# water-meter.net
KiCad netlist of a schematic drawn in Altium Designer
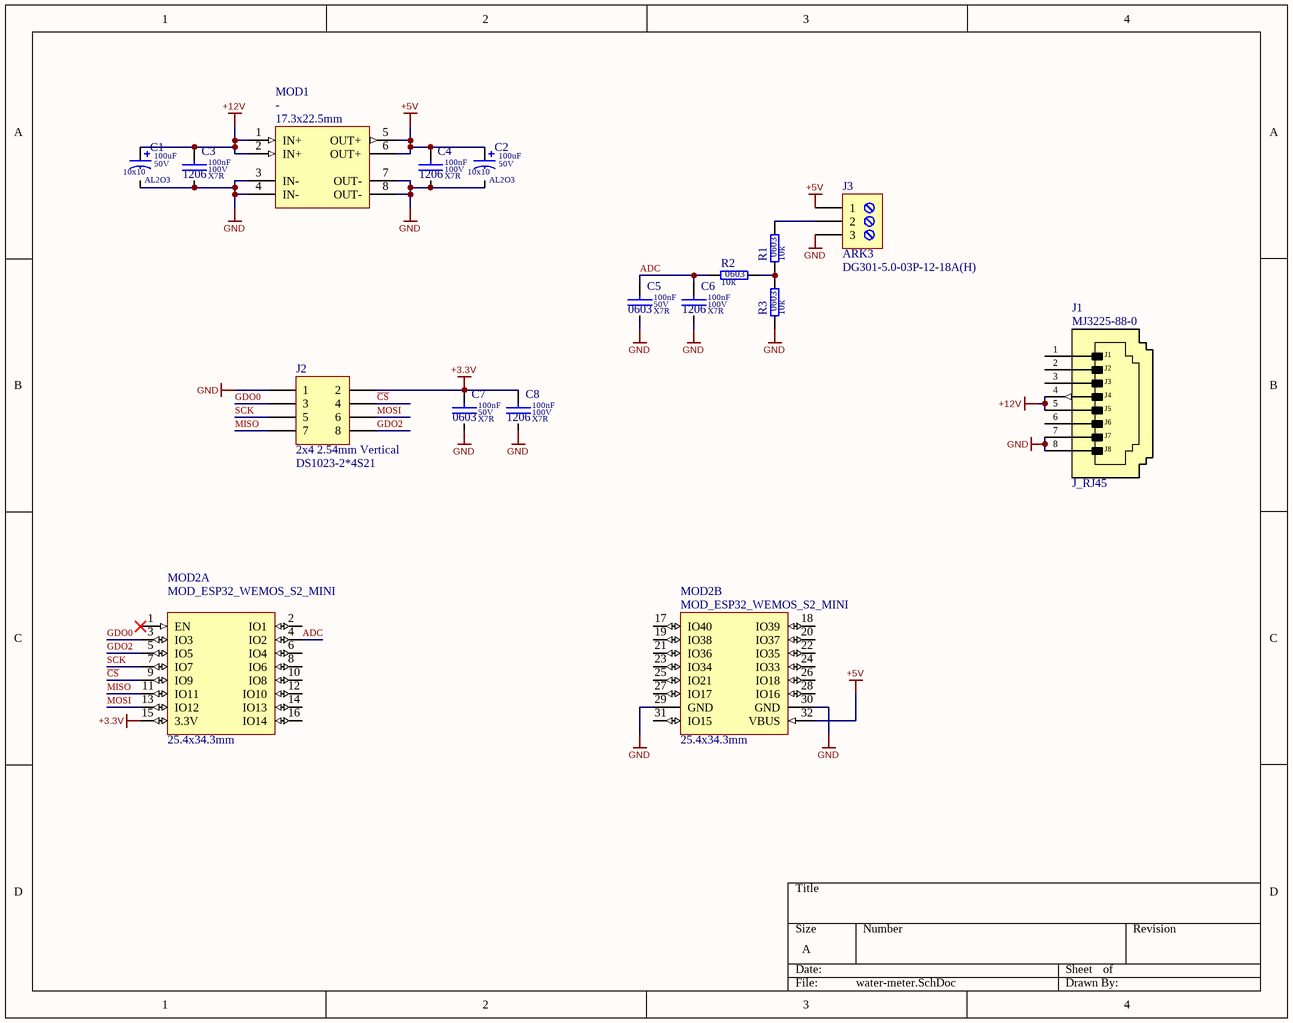
[diagram p0: water-meter.SchDoc]

(export (version "E")
  (design (tool "Eeschema 10.0.6"))
  (components
    (comp (ref "C1")
      (value "100uF")
      (footprint "CE_D_10x10_SMD")
      (description "Polarized Capacitor")
      (fields
        (field (name "DIELECTRIC") "AL2O3")
        (field (name "SCH_FOOTPRINT") "10x10")
        (field (name "VOLTAGE") "50V")
        (field (name "PART NUMBER") "CE_100uF_50V_AL2O3_10x10_20")
        (field (name "MANUFACTURER") "Nichicon")
      )
      (libsource (lib "Library") (part "CE"))
    )
    (comp (ref "C2")
      (value "100uF")
      (footprint "CE_D_10x10_SMD")
      (description "Polarized Capacitor")
      (fields
        (field (name "DIELECTRIC") "AL2O3")
        (field (name "SCH_FOOTPRINT") "10x10")
        (field (name "VOLTAGE") "50V")
        (field (name "PART NUMBER") "CE_100uF_50V_AL2O3_10x10_20")
        (field (name "MANUFACTURER") "Nichicon")
      )
      (libsource (lib "Library") (part "CE"))
    )
    (comp (ref "C3")
      (value "100nF")
      (footprint "C_1206_3216")
      (description "Capacitor")
      (fields
        (field (name "DIELECTRIC") "X7R")
        (field (name "VOLTAGE") "100V")
        (field (name "SCH_FOOTPRINT") "1206")
        (field (name "PART NUMBER") "C_100nF_100V_X7R_1206_10")
        (field (name "MANUFACTURER") "Samsung")
      )
      (libsource (lib "Library") (part "C"))
    )
    (comp (ref "C4")
      (value "100nF")
      (footprint "C_1206_3216")
      (description "Capacitor")
      (fields
        (field (name "DIELECTRIC") "X7R")
        (field (name "VOLTAGE") "100V")
        (field (name "SCH_FOOTPRINT") "1206")
        (field (name "PART NUMBER") "C_100nF_100V_X7R_1206_10")
        (field (name "MANUFACTURER") "Samsung")
      )
      (libsource (lib "Library") (part "C"))
    )
    (comp (ref "C5")
      (value "100nF")
      (footprint "C_0603_1608")
      (description "Capacitor")
      (fields
        (field (name "DIELECTRIC") "X7R")
        (field (name "VOLTAGE") "50V")
        (field (name "SCH_FOOTPRINT") "0603")
        (field (name "PART NUMBER") "C_100nF_50V_X7R_0603_10_AECQ1")
        (field (name "MANUFACTURER") "Murata")
      )
      (libsource (lib "Library") (part "C"))
    )
    (comp (ref "C6")
      (value "100nF")
      (footprint "C_1206_3216")
      (description "Capacitor")
      (fields
        (field (name "DIELECTRIC") "X7R")
        (field (name "VOLTAGE") "100V")
        (field (name "SCH_FOOTPRINT") "1206")
        (field (name "PART NUMBER") "C_100nF_100V_X7R_1206_10")
        (field (name "MANUFACTURER") "Samsung")
      )
      (libsource (lib "Library") (part "C"))
    )
    (comp (ref "C7")
      (value "100nF")
      (footprint "C_0603_1608")
      (description "Capacitor")
      (fields
        (field (name "DIELECTRIC") "X7R")
        (field (name "VOLTAGE") "50V")
        (field (name "SCH_FOOTPRINT") "0603")
        (field (name "PART NUMBER") "C_100nF_50V_X7R_0603_10_AECQ1")
        (field (name "MANUFACTURER") "Murata")
      )
      (libsource (lib "Library") (part "C"))
    )
    (comp (ref "C8")
      (value "100nF")
      (footprint "C_1206_3216")
      (description "Capacitor")
      (fields
        (field (name "DIELECTRIC") "X7R")
        (field (name "VOLTAGE") "100V")
        (field (name "SCH_FOOTPRINT") "1206")
        (field (name "PART NUMBER") "C_100nF_100V_X7R_1206_10")
        (field (name "MANUFACTURER") "Samsung")
      )
      (libsource (lib "Library") (part "C"))
    )
    (comp (ref "J1")
      (value "MJ3225-88-0")
      (footprint "J_RJ45_MJ3225-88-0")
      (fields
        (field (name "SCH_FOOTPRINT") "J_RJ45")
        (field (name "PART NUMBER") "J_RJ45_MJ3225-88-0")
        (field (name "MANUFACTURER") "Global Connector Technology")
        (field (name "Comment") "Modular Connector, Modular Jack, 1 x 1 (Port), 8P8C, Cat3")
      )
      (libsource (lib "Library") (part "J_RJ45"))
    )
    (comp (ref "J2")
      (value "DS1023-2*4S21")
      (footprint "J_HEADER_2x4_2.54_VERTICAL")
      (description "Pin Header")
      (fields
        (field (name "SCH_FOOTPRINT") "2x4 2.54mm Vertical")
        (field (name "PART NUMBER") "J_HEADER_2x4_2.54_VERTICAL")
        (field (name "MANUFACTURER") "Connfly")
      )
      (libsource (lib "Library") (part "J_HEADER_2x4"))
    )
    (comp (ref "J3")
      (value "DG301-5.0-03P-12-18A(H)")
      (footprint "J_ARK3")
      (description "ARK Screw terminal, 3-Pin")
      (fields
        (field (name "SCH_FOOTPRINT") "ARK3")
        (field (name "PART NUMBER") "J_TB-5.0-P-3P")
        (field (name "MANUFACTURER") "DEGSON ELECTRONICS")
      )
      (libsource (lib "Library") (part "J_ARK3"))
    )
    (comp (ref "MOD1")
      (value "-")
      (footprint "MOD_BUCK_MP1584")
      (fields
        (field (name "SCH_FOOTPRINT") "17.3x22.5mm")
        (field (name "PART NUMBER") "MOD_BUCK_MP1584")
        (field (name "Comment") "Low cost, Aliexpress-ready DC-DC buck converter using MP1584")
      )
      (libsource (lib "Library") (part "MOD_BUCK_MP1584"))
    )
    (comp (ref "MOD2")
      (value "MOD_ESP32_WEMOS_S2_MINI")
      (footprint "MOD_ESP32_WEMOS_S2_MINI")
      (fields
        (field (name "SCH_FOOTPRINT") "25.4x34.3mm")
        (field (name "MANUFACTURER") "Wemos")
        (field (name "Comment") "ESP32-S2FN4R2 mini wifi board")
      )
      (libsource (lib "Library") (part "MOD_ESP32_WEMOS_S2_MINI"))
    )
    (comp (ref "R1")
      (value "10k")
      (footprint "R_0603_1608")
      (fields
        (field (name "SCH_FOOTPRINT") "0603")
        (field (name "PART NUMBER") "R_10k_0603_1_AECQ0")
        (field (name "VOLTAGE") "75V")
        (field (name "POWER") "100mW")
      )
      (libsource (lib "Library") (part "R"))
    )
    (comp (ref "R2")
      (value "10k")
      (footprint "R_0603_1608")
      (fields
        (field (name "SCH_FOOTPRINT") "0603")
        (field (name "PART NUMBER") "R_10k_0603_1_AECQ0")
        (field (name "VOLTAGE") "75V")
        (field (name "POWER") "100mW")
      )
      (libsource (lib "Library") (part "R"))
    )
    (comp (ref "R3")
      (value "10k")
      (footprint "R_0603_1608")
      (fields
        (field (name "SCH_FOOTPRINT") "0603")
        (field (name "PART NUMBER") "R_10k_0603_1_AECQ0")
        (field (name "VOLTAGE") "75V")
        (field (name "POWER") "100mW")
      )
      (libsource (lib "Library") (part "R"))
    )
  )
  (nets
    (net (code "1") (name "+3.3V") (class "Default")
      (node (ref "C7") (pin "1") (pinfunction "1_1") (pintype "passive"))
      (node (ref "C8") (pin "1") (pinfunction "1_1") (pintype "passive"))
      (node (ref "J2") (pin "2") (pinfunction "2_2") (pintype "passive"))
      (node (ref "MOD2") (pin "15") (pinfunction "3.3V_15") (pintype "bidirectional"))
    )
    (net (code "2") (name "+5V") (class "Default")
      (node (ref "C2") (pin "1") (pinfunction "1_1") (pintype "passive"))
      (node (ref "C4") (pin "1") (pinfunction "1_1") (pintype "passive"))
      (node (ref "J3") (pin "1") (pinfunction "1_1") (pintype "passive"))
      (node (ref "MOD1") (pin "5") (pinfunction "OUT+_5") (pintype "output"))
      (node (ref "MOD1") (pin "6") (pinfunction "OUT+_6") (pintype "passive"))
      (node (ref "MOD2") (pin "32") (pinfunction "VBUS_32") (pintype "input"))
    )
    (net (code "3") (name "+12V") (class "Default")
      (node (ref "C1") (pin "1") (pinfunction "1_1") (pintype "passive"))
      (node (ref "C3") (pin "1") (pinfunction "1_1") (pintype "passive"))
      (node (ref "J1") (pin "4") (pintype "output"))
      (node (ref "J1") (pin "5") (pintype "passive"))
      (node (ref "MOD1") (pin "1") (pinfunction "IN+_1") (pintype "input"))
      (node (ref "MOD1") (pin "2") (pinfunction "IN+_2") (pintype "input"))
    )
    (net (code "4") (name "/ADC") (class "Default")
      (node (ref "C5") (pin "1") (pinfunction "1_1") (pintype "passive"))
      (node (ref "C6") (pin "1") (pinfunction "1_1") (pintype "passive"))
      (node (ref "MOD2") (pin "4") (pinfunction "IO2_4") (pintype "bidirectional"))
      (node (ref "R2") (pin "1") (pinfunction "1_1") (pintype "passive"))
    )
    (net (code "5") (name "/CS") (class "Default")
      (node (ref "J2") (pin "4") (pinfunction "4_4") (pintype "passive"))
      (node (ref "MOD2") (pin "9") (pinfunction "IO9_9") (pintype "bidirectional"))
    )
    (net (code "6") (name "/GDO0") (class "Default")
      (node (ref "J2") (pin "3") (pinfunction "3_3") (pintype "passive"))
      (node (ref "MOD2") (pin "3") (pinfunction "IO3_3") (pintype "bidirectional"))
    )
    (net (code "7") (name "/GDO2") (class "Default")
      (node (ref "J2") (pin "8") (pinfunction "8_8") (pintype "passive"))
      (node (ref "MOD2") (pin "5") (pinfunction "IO5_5") (pintype "bidirectional"))
    )
    (net (code "8") (name "/MISO") (class "Default")
      (node (ref "J2") (pin "7") (pinfunction "7_7") (pintype "passive"))
      (node (ref "MOD2") (pin "11") (pinfunction "IO11_11") (pintype "bidirectional"))
    )
    (net (code "9") (name "/MOSI") (class "Default")
      (node (ref "J2") (pin "6") (pinfunction "6_6") (pintype "passive"))
      (node (ref "MOD2") (pin "13") (pinfunction "IO12_13") (pintype "bidirectional"))
    )
    (net (code "10") (name "/SCK") (class "Default")
      (node (ref "J2") (pin "5") (pinfunction "5_5") (pintype "passive"))
      (node (ref "MOD2") (pin "7") (pinfunction "IO7_7") (pintype "bidirectional"))
    )
    (net (code "11") (name "GND") (class "Default")
      (node (ref "C1") (pin "2") (pinfunction "2_2") (pintype "passive"))
      (node (ref "C2") (pin "2") (pinfunction "2_2") (pintype "passive"))
      (node (ref "C3") (pin "2") (pinfunction "2_2") (pintype "passive"))
      (node (ref "C4") (pin "2") (pinfunction "2_2") (pintype "passive"))
      (node (ref "C5") (pin "2") (pinfunction "2_2") (pintype "passive"))
      (node (ref "C6") (pin "2") (pinfunction "2_2") (pintype "passive"))
      (node (ref "C7") (pin "2") (pinfunction "2_2") (pintype "passive"))
      (node (ref "C8") (pin "2") (pinfunction "2_2") (pintype "passive"))
      (node (ref "J1") (pin "7") (pintype "passive"))
      (node (ref "J1") (pin "8") (pintype "passive"))
      (node (ref "J2") (pin "1") (pinfunction "1_1") (pintype "passive"))
      (node (ref "J3") (pin "3") (pinfunction "3_3") (pintype "passive"))
      (node (ref "MOD1") (pin "3") (pinfunction "IN-_3") (pintype "power_in"))
      (node (ref "MOD1") (pin "4") (pinfunction "IN-_4") (pintype "power_in"))
      (node (ref "MOD1") (pin "7") (pinfunction "OUT-_7") (pintype "power_in"))
      (node (ref "MOD1") (pin "8") (pinfunction "OUT-_8") (pintype "power_in"))
      (node (ref "MOD2") (pin "29") (pinfunction "GND_29") (pintype "power_in"))
      (node (ref "MOD2") (pin "30") (pinfunction "GND_30") (pintype "power_in"))
      (node (ref "R3") (pin "1") (pinfunction "1_1") (pintype "passive"))
    )
    (net (code "12") (name "Net-(J3-Pad2)") (class "Default")
      (node (ref "J3") (pin "2") (pinfunction "2_2") (pintype "passive"))
      (node (ref "R1") (pin "2") (pinfunction "2_2") (pintype "passive"))
    )
    (net (code "13") (name "Net-(R1-Pad1)") (class "Default")
      (node (ref "R1") (pin "1") (pinfunction "1_1") (pintype "passive"))
      (node (ref "R2") (pin "2") (pinfunction "2_2") (pintype "passive"))
      (node (ref "R3") (pin "2") (pinfunction "2_2") (pintype "passive"))
    )
    (net (code "14") (name "unconnected-(J1-Pad1)") (class "Default")
      (node (ref "J1") (pin "1") (pintype "passive"))
    )
    (net (code "15") (name "unconnected-(J1-Pad2)") (class "Default")
      (node (ref "J1") (pin "2") (pintype "passive"))
    )
    (net (code "16") (name "unconnected-(J1-Pad3)") (class "Default")
      (node (ref "J1") (pin "3") (pintype "passive"))
    )
    (net (code "17") (name "unconnected-(J1-Pad6)") (class "Default")
      (node (ref "J1") (pin "6") (pintype "passive"))
    )
    (net (code "18") (name "unconnected-(MOD2A-EN-Pad1)") (class "Default")
      (node (ref "MOD2") (pin "1") (pinfunction "EN_1") (pintype "input+no_connect"))
    )
    (net (code "19") (name "unconnected-(MOD2A-IO1-Pad2)") (class "Default")
      (node (ref "MOD2") (pin "2") (pinfunction "IO1_2") (pintype "bidirectional"))
    )
    (net (code "20") (name "unconnected-(MOD2A-IO4-Pad6)") (class "Default")
      (node (ref "MOD2") (pin "6") (pinfunction "IO4_6") (pintype "bidirectional"))
    )
    (net (code "21") (name "unconnected-(MOD2A-IO6-Pad8)") (class "Default")
      (node (ref "MOD2") (pin "8") (pinfunction "IO6_8") (pintype "bidirectional"))
    )
    (net (code "22") (name "unconnected-(MOD2A-IO8-Pad10)") (class "Default")
      (node (ref "MOD2") (pin "10") (pinfunction "IO8_10") (pintype "bidirectional"))
    )
    (net (code "23") (name "unconnected-(MOD2A-IO10-Pad12)") (class "Default")
      (node (ref "MOD2") (pin "12") (pinfunction "IO10_12") (pintype "bidirectional"))
    )
    (net (code "24") (name "unconnected-(MOD2A-IO13-Pad14)") (class "Default")
      (node (ref "MOD2") (pin "14") (pinfunction "IO13_14") (pintype "bidirectional"))
    )
    (net (code "25") (name "unconnected-(MOD2A-IO14-Pad16)") (class "Default")
      (node (ref "MOD2") (pin "16") (pinfunction "IO14_16") (pintype "bidirectional"))
    )
    (net (code "26") (name "unconnected-(MOD2B-IO15-Pad31)") (class "Default")
      (node (ref "MOD2") (pin "31") (pinfunction "IO15_31") (pintype "bidirectional"))
    )
    (net (code "27") (name "unconnected-(MOD2B-IO16-Pad28)") (class "Default")
      (node (ref "MOD2") (pin "28") (pinfunction "IO16_28") (pintype "bidirectional"))
    )
    (net (code "28") (name "unconnected-(MOD2B-IO17-Pad27)") (class "Default")
      (node (ref "MOD2") (pin "27") (pinfunction "IO17_27") (pintype "bidirectional"))
    )
    (net (code "29") (name "unconnected-(MOD2B-IO18-Pad26)") (class "Default")
      (node (ref "MOD2") (pin "26") (pinfunction "IO18_26") (pintype "bidirectional"))
    )
    (net (code "30") (name "unconnected-(MOD2B-IO21-Pad25)") (class "Default")
      (node (ref "MOD2") (pin "25") (pinfunction "IO21_25") (pintype "bidirectional"))
    )
    (net (code "31") (name "unconnected-(MOD2B-IO33-Pad24)") (class "Default")
      (node (ref "MOD2") (pin "24") (pinfunction "IO33_24") (pintype "bidirectional"))
    )
    (net (code "32") (name "unconnected-(MOD2B-IO34-Pad23)") (class "Default")
      (node (ref "MOD2") (pin "23") (pinfunction "IO34_23") (pintype "bidirectional"))
    )
    (net (code "33") (name "unconnected-(MOD2B-IO35-Pad22)") (class "Default")
      (node (ref "MOD2") (pin "22") (pinfunction "IO35_22") (pintype "bidirectional"))
    )
    (net (code "34") (name "unconnected-(MOD2B-IO36-Pad21)") (class "Default")
      (node (ref "MOD2") (pin "21") (pinfunction "IO36_21") (pintype "bidirectional"))
    )
    (net (code "35") (name "unconnected-(MOD2B-IO37-Pad20)") (class "Default")
      (node (ref "MOD2") (pin "20") (pinfunction "IO37_20") (pintype "bidirectional"))
    )
    (net (code "36") (name "unconnected-(MOD2B-IO38-Pad19)") (class "Default")
      (node (ref "MOD2") (pin "19") (pinfunction "IO38_19") (pintype "bidirectional"))
    )
    (net (code "37") (name "unconnected-(MOD2B-IO39-Pad18)") (class "Default")
      (node (ref "MOD2") (pin "18") (pinfunction "IO39_18") (pintype "bidirectional"))
    )
    (net (code "38") (name "unconnected-(MOD2B-IO40-Pad17)") (class "Default")
      (node (ref "MOD2") (pin "17") (pinfunction "IO40_17") (pintype "bidirectional"))
    )
  )
)
